# JoyStickAdcInput.net
KiCad netlist of a schematic drawn in Altium Designer
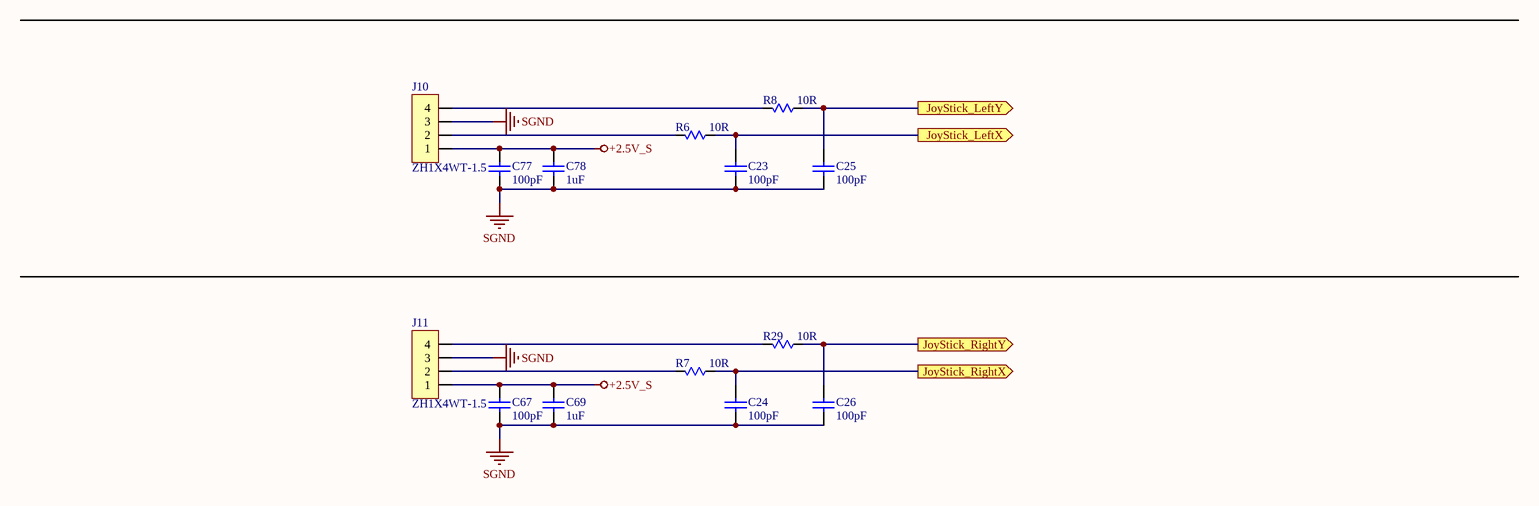
[diagram p0: JoyStickAdcInput.SchDoc]

(export (version "E")
  (design (tool "Eeschema 10.0.6"))
  (components
    (comp (ref "C23")
      (value "100pF")
      (footprint "C0805")
      (description "Capacitor")
      (fields (field (name "PUBLISHER") "Altium Limited"))
      (libsource (lib "Miscellaneous Devices") (part "Cap"))
    )
    (comp (ref "C24")
      (value "100pF")
      (footprint "C0805")
      (description "Capacitor")
      (fields (field (name "PUBLISHER") "Altium Limited"))
      (libsource (lib "Miscellaneous Devices") (part "Cap"))
    )
    (comp (ref "C25")
      (value "100pF")
      (footprint "C0805")
      (description "Capacitor")
      (fields (field (name "PUBLISHER") "Altium Limited"))
      (libsource (lib "Miscellaneous Devices") (part "Cap"))
    )
    (comp (ref "C26")
      (value "100pF")
      (footprint "C0805")
      (description "Capacitor")
      (fields (field (name "PUBLISHER") "Altium Limited"))
      (libsource (lib "Miscellaneous Devices") (part "Cap"))
    )
    (comp (ref "C67")
      (value "100pF")
      (footprint "C0805")
      (description "Capacitor")
      (fields (field (name "PUBLISHER") "Altium Limited"))
      (libsource (lib "Miscellaneous Devices") (part "Cap"))
    )
    (comp (ref "C69")
      (value "1uF")
      (footprint "C0805")
      (description "Capacitor")
      (fields (field (name "PUBLISHER") "Altium Limited"))
      (libsource (lib "Miscellaneous Devices") (part "Cap"))
    )
    (comp (ref "C77")
      (value "100pF")
      (footprint "C0805")
      (description "Capacitor")
      (fields (field (name "PUBLISHER") "Altium Limited"))
      (libsource (lib "Miscellaneous Devices") (part "Cap"))
    )
    (comp (ref "C78")
      (value "1uF")
      (footprint "C0805")
      (description "Capacitor")
      (fields (field (name "PUBLISHER") "Altium Limited"))
      (libsource (lib "Miscellaneous Devices") (part "Cap"))
    )
    (comp (ref "J10")
      (value "ZH1X4WT-1.5")
      (footprint "ZH1X4WT-1.5")
      (libsource (lib "Connector Class") (part "HEADER1X4"))
    )
    (comp (ref "J11")
      (value "ZH1X4WT-1.5")
      (footprint "ZH1X4WT-1.5")
      (libsource (lib "Connector Class") (part "HEADER1X4"))
    )
    (comp (ref "R6")
      (value "10R")
      (footprint "R0805")
      (description "Resistor")
      (fields (field (name "PUBLISHER") "Altium Limited"))
      (libsource (lib "Passive Components Class") (part "RES"))
    )
    (comp (ref "R7")
      (value "10R")
      (footprint "R0805")
      (description "Resistor")
      (fields (field (name "PUBLISHER") "Altium Limited"))
      (libsource (lib "Passive Components Class") (part "RES"))
    )
    (comp (ref "R8")
      (value "10R")
      (footprint "R0805")
      (description "Resistor")
      (fields (field (name "PUBLISHER") "Altium Limited"))
      (libsource (lib "Passive Components Class") (part "RES"))
    )
    (comp (ref "R29")
      (value "10R")
      (footprint "R0805")
      (description "Resistor")
      (fields (field (name "PUBLISHER") "Altium Limited"))
      (libsource (lib "Passive Components Class") (part "RES"))
    )
  )
  (nets
    (net (code "1") (name "+2.5V_S") (class "Default")
      (node (ref "C67") (pin "1") (pinfunction "1_1") (pintype "passive"))
      (node (ref "C69") (pin "1") (pinfunction "1_1") (pintype "passive"))
      (node (ref "C77") (pin "1") (pinfunction "1_1") (pintype "passive"))
      (node (ref "C78") (pin "1") (pinfunction "1_1") (pintype "passive"))
      (node (ref "J10") (pin "1") (pinfunction "1_1") (pintype "passive"))
      (node (ref "J11") (pin "1") (pinfunction "1_1") (pintype "passive"))
    )
    (net (code "2") (name "/JoyStick_LeftX") (class "Default")
      (node (ref "C23") (pin "1") (pinfunction "1_1") (pintype "passive"))
      (node (ref "R6") (pin "1") (pinfunction "1_1") (pintype "passive"))
    )
    (net (code "3") (name "/JoyStick_LeftY") (class "Default")
      (node (ref "C25") (pin "1") (pinfunction "1_1") (pintype "passive"))
      (node (ref "R8") (pin "1") (pinfunction "1_1") (pintype "passive"))
    )
    (net (code "4") (name "/JoyStick_RightX") (class "Default")
      (node (ref "C24") (pin "1") (pinfunction "1_1") (pintype "passive"))
      (node (ref "R7") (pin "1") (pinfunction "1_1") (pintype "passive"))
    )
    (net (code "5") (name "/JoyStick_RightY") (class "Default")
      (node (ref "C26") (pin "1") (pinfunction "1_1") (pintype "passive"))
      (node (ref "R29") (pin "1") (pinfunction "1_1") (pintype "passive"))
    )
    (net (code "6") (name "Net-(J10-Pad2)") (class "Default")
      (node (ref "J10") (pin "2") (pinfunction "2_2") (pintype "passive"))
      (node (ref "R6") (pin "2") (pinfunction "2_2") (pintype "passive"))
    )
    (net (code "7") (name "Net-(J10-Pad4)") (class "Default")
      (node (ref "J10") (pin "4") (pinfunction "4_4") (pintype "passive"))
      (node (ref "R8") (pin "2") (pinfunction "2_2") (pintype "passive"))
    )
    (net (code "8") (name "Net-(J11-Pad2)") (class "Default")
      (node (ref "J11") (pin "2") (pinfunction "2_2") (pintype "passive"))
      (node (ref "R7") (pin "2") (pinfunction "2_2") (pintype "passive"))
    )
    (net (code "9") (name "Net-(J11-Pad4)") (class "Default")
      (node (ref "J11") (pin "4") (pinfunction "4_4") (pintype "passive"))
      (node (ref "R29") (pin "2") (pinfunction "2_2") (pintype "passive"))
    )
    (net (code "10") (name "SGND") (class "Default")
      (node (ref "C23") (pin "2") (pinfunction "2_2") (pintype "passive"))
      (node (ref "C24") (pin "2") (pinfunction "2_2") (pintype "passive"))
      (node (ref "C25") (pin "2") (pinfunction "2_2") (pintype "passive"))
      (node (ref "C26") (pin "2") (pinfunction "2_2") (pintype "passive"))
      (node (ref "C67") (pin "2") (pinfunction "2_2") (pintype "passive"))
      (node (ref "C69") (pin "2") (pinfunction "2_2") (pintype "passive"))
      (node (ref "C77") (pin "2") (pinfunction "2_2") (pintype "passive"))
      (node (ref "C78") (pin "2") (pinfunction "2_2") (pintype "passive"))
      (node (ref "J10") (pin "3") (pinfunction "3_3") (pintype "passive"))
      (node (ref "J11") (pin "3") (pinfunction "3_3") (pintype "passive"))
    )
  )
)
